# Electronic_Power_System_EV1.net
KiCad netlist of a schematic drawn in EAGLE
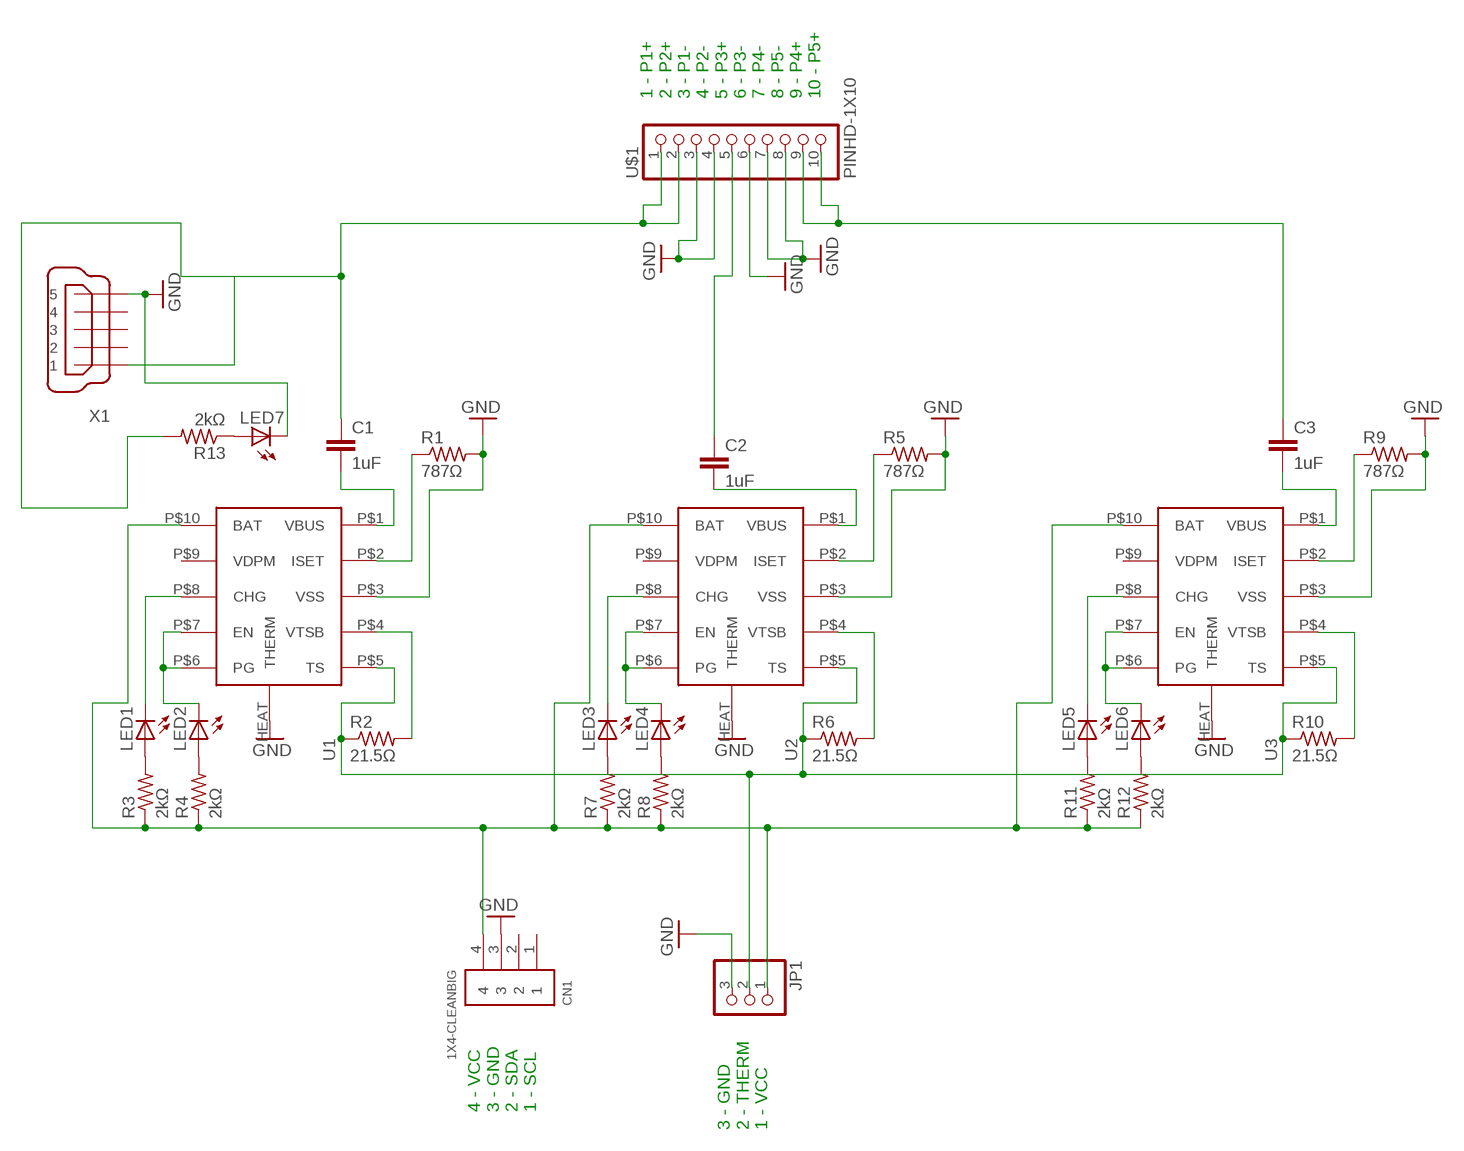
[diagram p0: schematic, sheet 1]

(export (version "E")
  (design (tool "Eeschema 10.0.6"))
  (components
    (comp (ref "C1")
      (value "1uF")
      (footprint "eagle-import:C0805")
      (libsource (lib "eagle-import") (part "C-EUC0805"))
    )
    (comp (ref "C2")
      (value "1uF")
      (footprint "eagle-import:C0805")
      (libsource (lib "eagle-import") (part "C-EUC0805"))
    )
    (comp (ref "C3")
      (value "1uF")
      (footprint "eagle-import:C0805")
      (libsource (lib "eagle-import") (part "C-EUC0805"))
    )
    (comp (ref "CN1")
      (value "1X4-CLEANBIG")
      (footprint "eagle-import:1X04-CLEANBIG")
      (libsource (lib "eagle-import") (part "1X4-CLEANBIG"))
    )
    (comp (ref "JP1")
      (value "PINHD-1X3")
      (footprint "eagle-import:1X03")
      (libsource (lib "eagle-import") (part "PINHD-1X3"))
    )
    (comp (ref "LED1")
      (value "LEDCHIPLED_0805")
      (footprint "eagle-import:CHIPLED_0805")
      (libsource (lib "eagle-import") (part "LEDCHIPLED_0805"))
    )
    (comp (ref "LED2")
      (value "LEDCHIPLED_0805")
      (footprint "eagle-import:CHIPLED_0805")
      (libsource (lib "eagle-import") (part "LEDCHIPLED_0805"))
    )
    (comp (ref "LED3")
      (value "LEDCHIPLED_0805")
      (footprint "eagle-import:CHIPLED_0805")
      (libsource (lib "eagle-import") (part "LEDCHIPLED_0805"))
    )
    (comp (ref "LED4")
      (value "LEDCHIPLED_0805")
      (footprint "eagle-import:CHIPLED_0805")
      (libsource (lib "eagle-import") (part "LEDCHIPLED_0805"))
    )
    (comp (ref "LED5")
      (value "LEDCHIPLED_0805")
      (footprint "eagle-import:CHIPLED_0805")
      (libsource (lib "eagle-import") (part "LEDCHIPLED_0805"))
    )
    (comp (ref "LED6")
      (value "LEDCHIPLED_0805")
      (footprint "eagle-import:CHIPLED_0805")
      (libsource (lib "eagle-import") (part "LEDCHIPLED_0805"))
    )
    (comp (ref "LED7")
      (value "LEDCHIPLED_0805")
      (footprint "eagle-import:CHIPLED_0805")
      (libsource (lib "eagle-import") (part "LEDCHIPLED_0805"))
    )
    (comp (ref "R1")
      (value "787Ω")
      (footprint "eagle-import:R0805")
      (libsource (lib "eagle-import") (part "R-US_R0805"))
    )
    (comp (ref "R2")
      (value "21.5Ω")
      (footprint "eagle-import:R0805")
      (libsource (lib "eagle-import") (part "R-US_R0805"))
    )
    (comp (ref "R3")
      (value "2kΩ")
      (footprint "eagle-import:R0805")
      (libsource (lib "eagle-import") (part "R-US_R0805"))
    )
    (comp (ref "R4")
      (value "2kΩ")
      (footprint "eagle-import:R0805")
      (libsource (lib "eagle-import") (part "R-US_R0805"))
    )
    (comp (ref "R5")
      (value "787Ω")
      (footprint "eagle-import:R0805")
      (libsource (lib "eagle-import") (part "R-US_R0805"))
    )
    (comp (ref "R6")
      (value "21.5Ω")
      (footprint "eagle-import:R0805")
      (libsource (lib "eagle-import") (part "R-US_R0805"))
    )
    (comp (ref "R7")
      (value "2kΩ")
      (footprint "eagle-import:R0805")
      (libsource (lib "eagle-import") (part "R-US_R0805"))
    )
    (comp (ref "R8")
      (value "2kΩ")
      (footprint "eagle-import:R0805")
      (libsource (lib "eagle-import") (part "R-US_R0805"))
    )
    (comp (ref "R9")
      (value "787Ω")
      (footprint "eagle-import:R0805")
      (libsource (lib "eagle-import") (part "R-US_R0805"))
    )
    (comp (ref "R10")
      (value "21.5Ω")
      (footprint "eagle-import:R0805")
      (libsource (lib "eagle-import") (part "R-US_R0805"))
    )
    (comp (ref "R11")
      (value "2kΩ")
      (footprint "eagle-import:R0805")
      (libsource (lib "eagle-import") (part "R-US_R0805"))
    )
    (comp (ref "R12")
      (value "2kΩ")
      (footprint "eagle-import:R0805")
      (libsource (lib "eagle-import") (part "R-US_R0805"))
    )
    (comp (ref "R13")
      (value "2kΩ")
      (footprint "eagle-import:R0805")
      (libsource (lib "eagle-import") (part "R-US_R0805"))
    )
    (comp (ref "U$1")
      (value "PINHD-1X10")
      (footprint "eagle-import:1X10-BIG")
      (libsource (lib "eagle-import") (part "PINHD-1X10"))
    )
    (comp (ref "U1")
      (value "BQ24210")
      (footprint "eagle-import:BQ24210")
      (libsource (lib "eagle-import") (part "BQ24210"))
    )
    (comp (ref "U2")
      (value "BQ24210")
      (footprint "eagle-import:BQ24210")
      (libsource (lib "eagle-import") (part "BQ24210"))
    )
    (comp (ref "U3")
      (value "BQ24210")
      (footprint "eagle-import:BQ24210")
      (libsource (lib "eagle-import") (part "BQ24210"))
    )
    (comp (ref "X1")
      (value "MINI-USB-UX60A-MB-5ST")
      (footprint "eagle-import:UX60A-MB-5ST")
      (libsource (lib "eagle-import") (part "MINI-USB-UX60A-MB-5ST"))
    )
  )
  (nets
    (net (code "1") (name "GND") (class "Default")
      (node (ref "CN1") (pin "3") (pinfunction "3_3") (pintype "bidirectional"))
      (node (ref "JP1") (pin "3") (pinfunction "3_3") (pintype "passive"))
      (node (ref "LED7") (pin "C") (pinfunction "C_C") (pintype "passive"))
      (node (ref "R1") (pin "2") (pinfunction "2_2") (pintype "passive"))
      (node (ref "R5") (pin "2") (pinfunction "2_2") (pintype "passive"))
      (node (ref "R9") (pin "2") (pinfunction "2_2") (pintype "passive"))
      (node (ref "U$1") (pin "3") (pinfunction "3_3") (pintype "passive"))
      (node (ref "U$1") (pin "4") (pinfunction "4_4") (pintype "passive"))
      (node (ref "U$1") (pin "6") (pinfunction "6_6") (pintype "passive"))
      (node (ref "U$1") (pin "7") (pinfunction "7_7") (pintype "passive"))
      (node (ref "U$1") (pin "8") (pinfunction "8_8") (pintype "passive"))
      (node (ref "U1") (pin "HEAT") (pinfunction "THERM_HEAT") (pintype "power_in"))
      (node (ref "U1") (pin "P$3") (pinfunction "VSS_P$3") (pintype "power_in"))
      (node (ref "U2") (pin "HEAT") (pinfunction "THERM_HEAT") (pintype "power_in"))
      (node (ref "U2") (pin "P$3") (pinfunction "VSS_P$3") (pintype "power_in"))
      (node (ref "U3") (pin "HEAT") (pinfunction "THERM_HEAT") (pintype "power_in"))
      (node (ref "U3") (pin "P$3") (pinfunction "VSS_P$3") (pintype "power_in"))
      (node (ref "X1") (pin "5") (pinfunction "5_5") (pintype "input"))
    )
    (net (code "2") (name "Net-(C1-Pad1)") (class "Default")
      (node (ref "C1") (pin "1") (pinfunction "1_1") (pintype "passive"))
      (node (ref "R13") (pin "2") (pinfunction "2_2") (pintype "passive"))
      (node (ref "U$1") (pin "1") (pinfunction "1_1") (pintype "passive"))
      (node (ref "U$1") (pin "2") (pinfunction "2_2") (pintype "passive"))
      (node (ref "X1") (pin "1") (pinfunction "1_1") (pintype "input"))
    )
    (net (code "3") (name "Net-(C2-Pad1)") (class "Default")
      (node (ref "C2") (pin "1") (pinfunction "1_1") (pintype "passive"))
      (node (ref "U$1") (pin "5") (pinfunction "5_5") (pintype "passive"))
    )
    (net (code "4") (name "Net-(C3-Pad1)") (class "Default")
      (node (ref "C3") (pin "1") (pinfunction "1_1") (pintype "passive"))
      (node (ref "U$1") (pin "10") (pinfunction "10_10") (pintype "passive"))
      (node (ref "U$1") (pin "9") (pinfunction "9_9") (pintype "passive"))
    )
    (net (code "5") (name "Net-(LED1-PadA)") (class "Default")
      (node (ref "LED1") (pin "A") (pinfunction "A_A") (pintype "passive"))
      (node (ref "R3") (pin "2") (pinfunction "2_2") (pintype "passive"))
    )
    (net (code "6") (name "Net-(LED2-PadA)") (class "Default")
      (node (ref "LED2") (pin "A") (pinfunction "A_A") (pintype "passive"))
      (node (ref "R4") (pin "2") (pinfunction "2_2") (pintype "passive"))
    )
    (net (code "7") (name "Net-(LED3-PadA)") (class "Default")
      (node (ref "LED3") (pin "A") (pinfunction "A_A") (pintype "passive"))
      (node (ref "R7") (pin "2") (pinfunction "2_2") (pintype "passive"))
    )
    (net (code "8") (name "Net-(LED4-PadA)") (class "Default")
      (node (ref "LED4") (pin "A") (pinfunction "A_A") (pintype "passive"))
      (node (ref "R8") (pin "2") (pinfunction "2_2") (pintype "passive"))
    )
    (net (code "9") (name "Net-(LED5-PadA)") (class "Default")
      (node (ref "LED5") (pin "A") (pinfunction "A_A") (pintype "passive"))
      (node (ref "R11") (pin "2") (pinfunction "2_2") (pintype "passive"))
    )
    (net (code "10") (name "Net-(LED6-PadA)") (class "Default")
      (node (ref "LED6") (pin "A") (pinfunction "A_A") (pintype "passive"))
      (node (ref "R12") (pin "2") (pinfunction "2_2") (pintype "passive"))
    )
    (net (code "11") (name "Net-(LED7-PadA)") (class "Default")
      (node (ref "LED7") (pin "A") (pinfunction "A_A") (pintype "passive"))
      (node (ref "R13") (pin "1") (pinfunction "1_1") (pintype "passive"))
    )
    (net (code "12") (name "Net-(U1-BAT)") (class "Default")
      (node (ref "CN1") (pin "4") (pinfunction "4_4") (pintype "bidirectional"))
      (node (ref "JP1") (pin "1") (pinfunction "1_1") (pintype "passive"))
      (node (ref "R11") (pin "1") (pinfunction "1_1") (pintype "passive"))
      (node (ref "R12") (pin "1") (pinfunction "1_1") (pintype "passive"))
      (node (ref "R3") (pin "1") (pinfunction "1_1") (pintype "passive"))
      (node (ref "R4") (pin "1") (pinfunction "1_1") (pintype "passive"))
      (node (ref "R7") (pin "1") (pinfunction "1_1") (pintype "passive"))
      (node (ref "R8") (pin "1") (pinfunction "1_1") (pintype "passive"))
      (node (ref "U1") (pin "P$10") (pinfunction "BAT_P$10") (pintype "bidirectional"))
      (node (ref "U2") (pin "P$10") (pinfunction "BAT_P$10") (pintype "bidirectional"))
      (node (ref "U3") (pin "P$10") (pinfunction "BAT_P$10") (pintype "bidirectional"))
    )
    (net (code "13") (name "Net-(U1-CHG)") (class "Default")
      (node (ref "LED1") (pin "C") (pinfunction "C_C") (pintype "passive"))
      (node (ref "U1") (pin "P$8") (pinfunction "CHG_P$8") (pintype "output"))
    )
    (net (code "14") (name "Net-(U1-EN)") (class "Default")
      (node (ref "LED2") (pin "C") (pinfunction "C_C") (pintype "passive"))
      (node (ref "U1") (pin "P$6") (pinfunction "PG_P$6") (pintype "output"))
      (node (ref "U1") (pin "P$7") (pinfunction "EN_P$7") (pintype "input"))
    )
    (net (code "15") (name "Net-(U1-ISET)") (class "Default")
      (node (ref "R1") (pin "1") (pinfunction "1_1") (pintype "passive"))
      (node (ref "U1") (pin "P$2") (pinfunction "ISET_P$2") (pintype "input"))
    )
    (net (code "16") (name "Net-(U1-TS)") (class "Default")
      (node (ref "JP1") (pin "2") (pinfunction "2_2") (pintype "passive"))
      (node (ref "R10") (pin "1") (pinfunction "1_1") (pintype "passive"))
      (node (ref "R2") (pin "1") (pinfunction "1_1") (pintype "passive"))
      (node (ref "R6") (pin "1") (pinfunction "1_1") (pintype "passive"))
      (node (ref "U1") (pin "P$5") (pinfunction "TS_P$5") (pintype "input"))
      (node (ref "U2") (pin "P$5") (pinfunction "TS_P$5") (pintype "input"))
      (node (ref "U3") (pin "P$5") (pinfunction "TS_P$5") (pintype "input"))
    )
    (net (code "17") (name "Net-(U1-VBUS)") (class "Default")
      (node (ref "C1") (pin "2") (pinfunction "2_2") (pintype "passive"))
      (node (ref "U1") (pin "P$1") (pinfunction "VBUS_P$1") (pintype "bidirectional"))
    )
    (net (code "18") (name "Net-(U1-VTSB)") (class "Default")
      (node (ref "R2") (pin "2") (pinfunction "2_2") (pintype "passive"))
      (node (ref "U1") (pin "P$4") (pinfunction "VTSB_P$4") (pintype "output"))
    )
    (net (code "19") (name "Net-(U2-CHG)") (class "Default")
      (node (ref "LED3") (pin "C") (pinfunction "C_C") (pintype "passive"))
      (node (ref "U2") (pin "P$8") (pinfunction "CHG_P$8") (pintype "output"))
    )
    (net (code "20") (name "Net-(U2-EN)") (class "Default")
      (node (ref "LED4") (pin "C") (pinfunction "C_C") (pintype "passive"))
      (node (ref "U2") (pin "P$6") (pinfunction "PG_P$6") (pintype "output"))
      (node (ref "U2") (pin "P$7") (pinfunction "EN_P$7") (pintype "input"))
    )
    (net (code "21") (name "Net-(U2-ISET)") (class "Default")
      (node (ref "R5") (pin "1") (pinfunction "1_1") (pintype "passive"))
      (node (ref "U2") (pin "P$2") (pinfunction "ISET_P$2") (pintype "input"))
    )
    (net (code "22") (name "Net-(U2-VBUS)") (class "Default")
      (node (ref "C2") (pin "2") (pinfunction "2_2") (pintype "passive"))
      (node (ref "U2") (pin "P$1") (pinfunction "VBUS_P$1") (pintype "bidirectional"))
    )
    (net (code "23") (name "Net-(U2-VTSB)") (class "Default")
      (node (ref "R6") (pin "2") (pinfunction "2_2") (pintype "passive"))
      (node (ref "U2") (pin "P$4") (pinfunction "VTSB_P$4") (pintype "output"))
    )
    (net (code "24") (name "Net-(U3-CHG)") (class "Default")
      (node (ref "LED5") (pin "C") (pinfunction "C_C") (pintype "passive"))
      (node (ref "U3") (pin "P$8") (pinfunction "CHG_P$8") (pintype "output"))
    )
    (net (code "25") (name "Net-(U3-EN)") (class "Default")
      (node (ref "LED6") (pin "C") (pinfunction "C_C") (pintype "passive"))
      (node (ref "U3") (pin "P$6") (pinfunction "PG_P$6") (pintype "output"))
      (node (ref "U3") (pin "P$7") (pinfunction "EN_P$7") (pintype "input"))
    )
    (net (code "26") (name "Net-(U3-ISET)") (class "Default")
      (node (ref "R9") (pin "1") (pinfunction "1_1") (pintype "passive"))
      (node (ref "U3") (pin "P$2") (pinfunction "ISET_P$2") (pintype "input"))
    )
    (net (code "27") (name "Net-(U3-VBUS)") (class "Default")
      (node (ref "C3") (pin "2") (pinfunction "2_2") (pintype "passive"))
      (node (ref "U3") (pin "P$1") (pinfunction "VBUS_P$1") (pintype "bidirectional"))
    )
    (net (code "28") (name "Net-(U3-VTSB)") (class "Default")
      (node (ref "R10") (pin "2") (pinfunction "2_2") (pintype "passive"))
      (node (ref "U3") (pin "P$4") (pinfunction "VTSB_P$4") (pintype "output"))
    )
    (net (code "29") (name "unconnected-(CN1-Pad1)") (class "Default")
      (node (ref "CN1") (pin "1") (pinfunction "1_1") (pintype "bidirectional"))
    )
    (net (code "30") (name "unconnected-(CN1-Pad2)") (class "Default")
      (node (ref "CN1") (pin "2") (pinfunction "2_2") (pintype "bidirectional"))
    )
    (net (code "31") (name "unconnected-(U1-VDPM-PadP$9)") (class "Default")
      (node (ref "U1") (pin "P$9") (pinfunction "VDPM_P$9") (pintype "input"))
    )
    (net (code "32") (name "unconnected-(U2-VDPM-PadP$9)") (class "Default")
      (node (ref "U2") (pin "P$9") (pinfunction "VDPM_P$9") (pintype "input"))
    )
    (net (code "33") (name "unconnected-(U3-VDPM-PadP$9)") (class "Default")
      (node (ref "U3") (pin "P$9") (pinfunction "VDPM_P$9") (pintype "input"))
    )
    (net (code "34") (name "unconnected-(X1-Pad2)") (class "Default")
      (node (ref "X1") (pin "2") (pinfunction "2_2") (pintype "input"))
    )
    (net (code "35") (name "unconnected-(X1-Pad3)") (class "Default")
      (node (ref "X1") (pin "3") (pinfunction "3_3") (pintype "input"))
    )
    (net (code "36") (name "unconnected-(X1-Pad4)") (class "Default")
      (node (ref "X1") (pin "4") (pinfunction "4_4") (pintype "input"))
    )
  )
)
